# SCH_Alarm_Robotics_PCB_Hacker_Card_2024-.net
KiCad netlist of a schematic drawn in EasyEDA
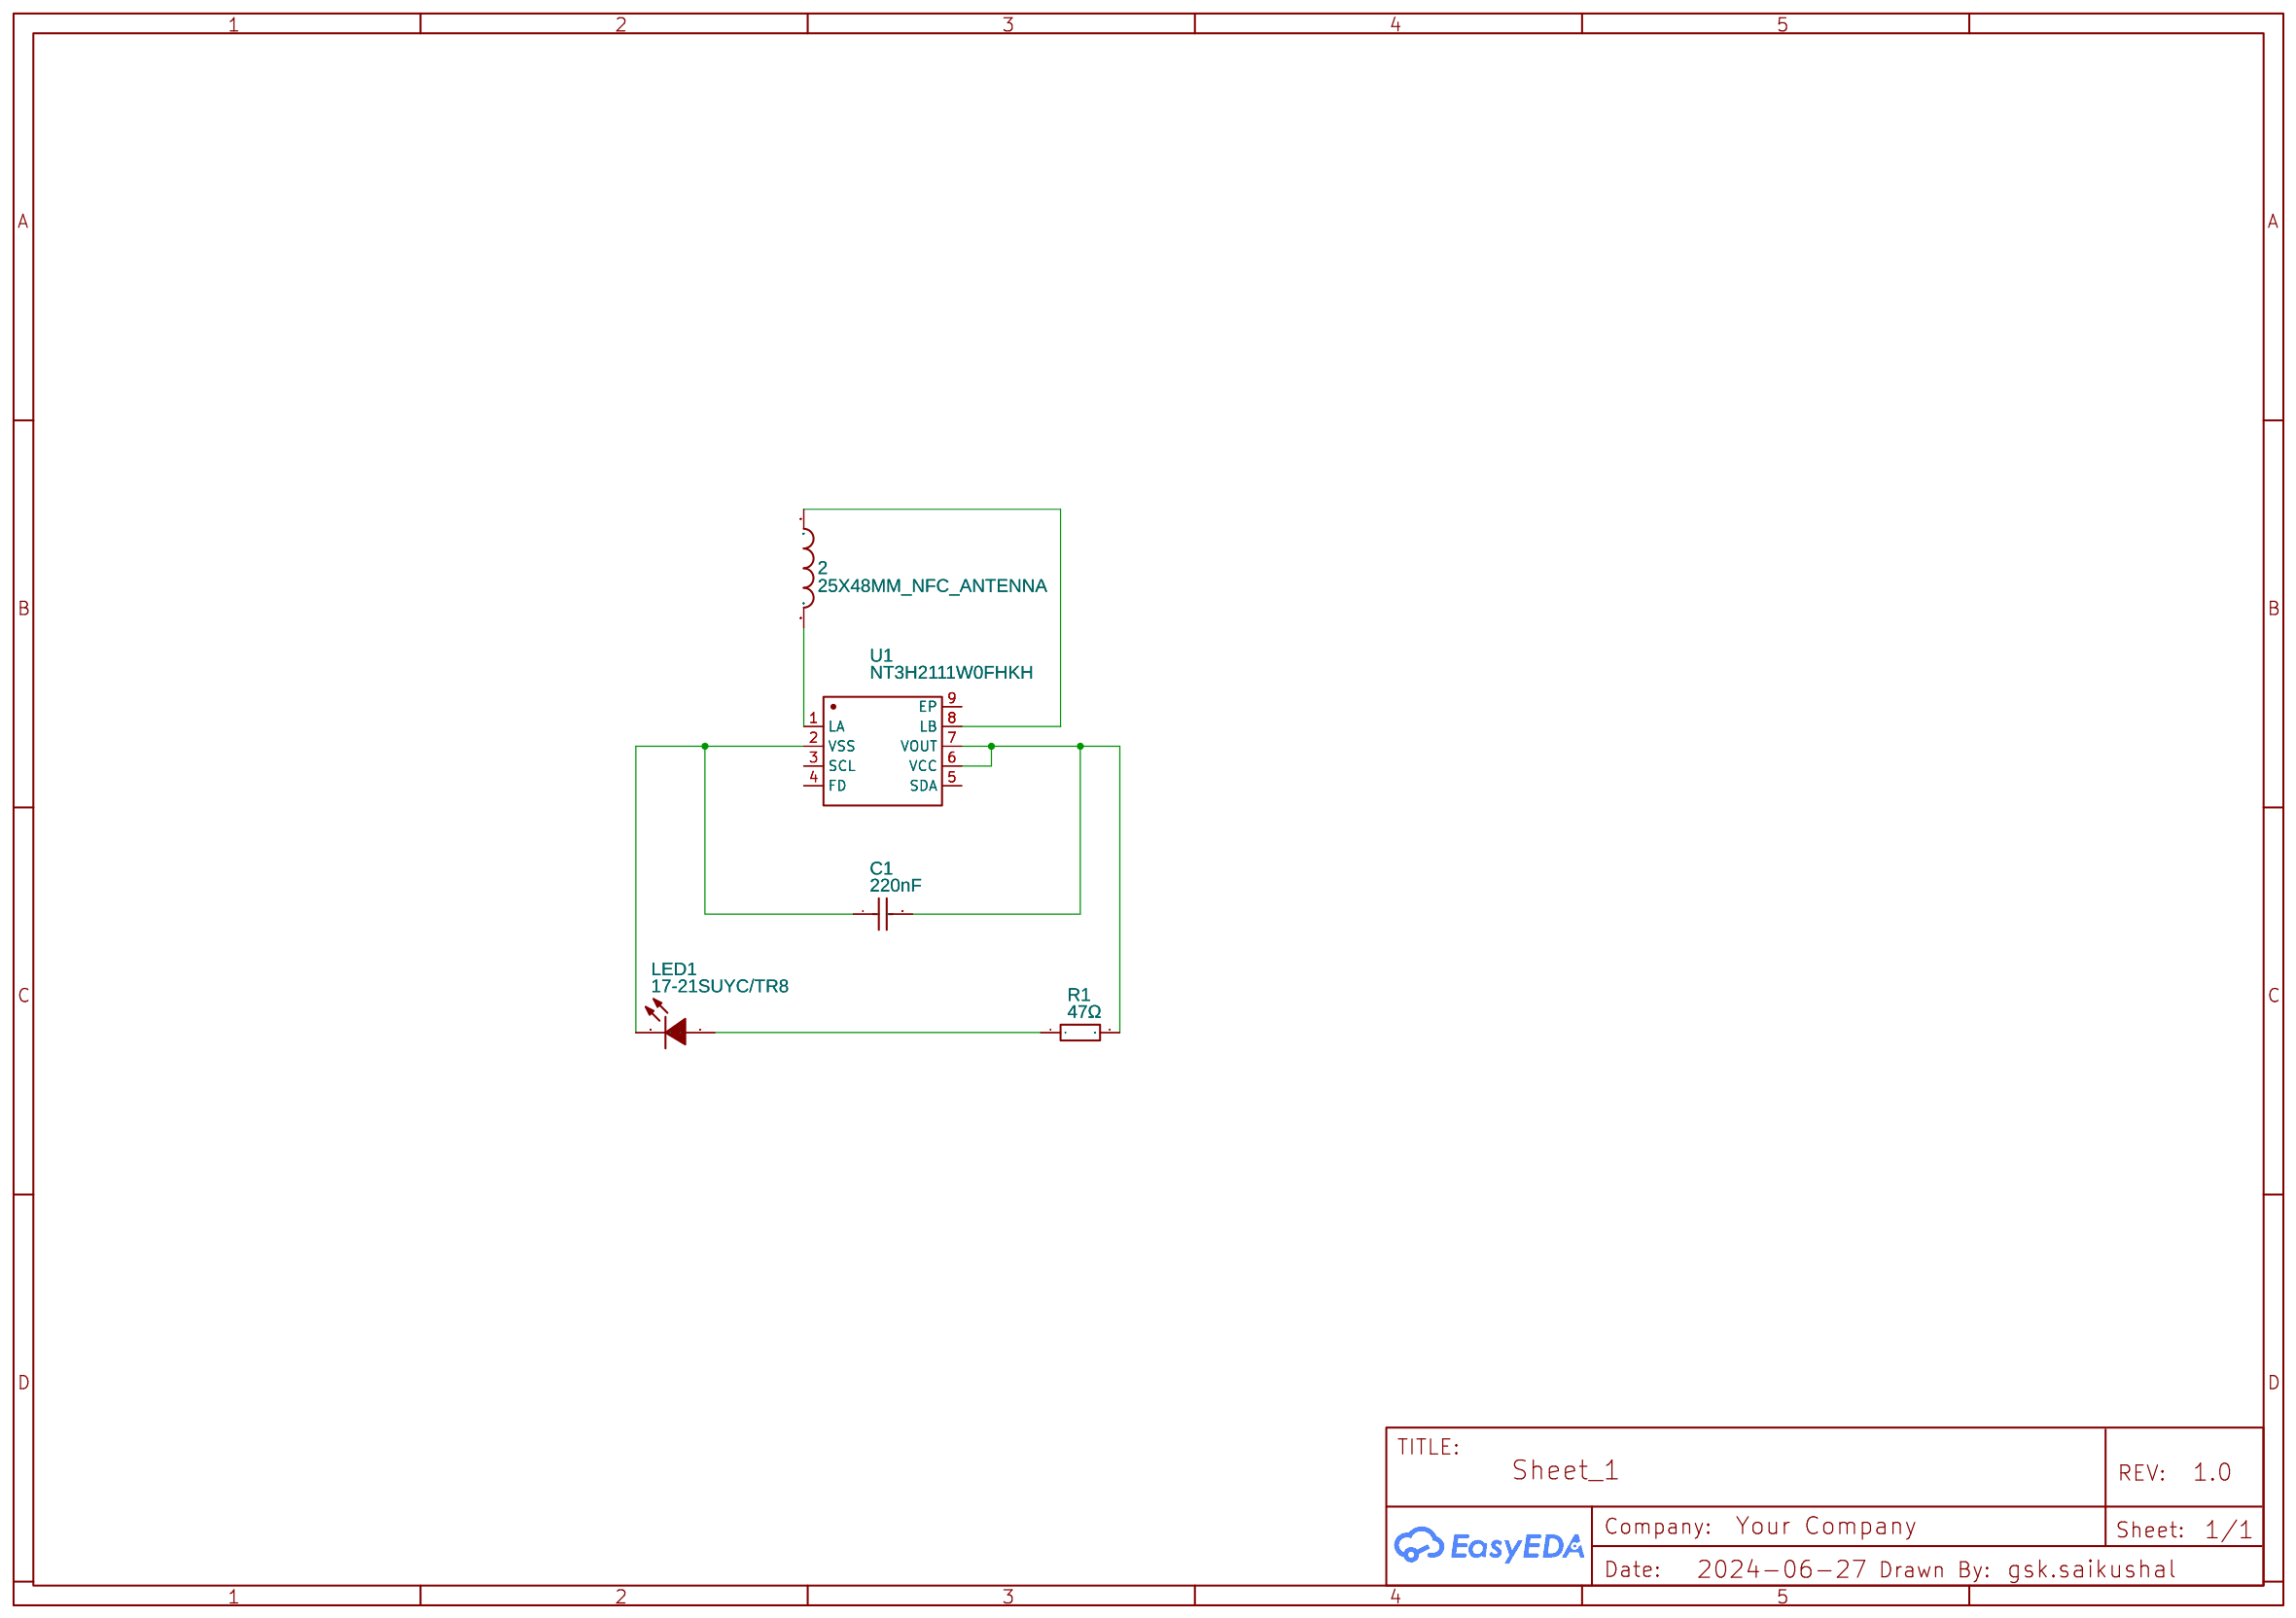
[diagram p0: schematic sheet]

(export (version "E")
  (design (tool "Eeschema 10.0.6"))
  (components
    (comp (ref "2") (value "25X48MM_NFC_ANTENNA") (libsource (lib "") (part "25X48MM_NFC_ANTENNA")))
    (comp (ref "C1")
      (value "220nF")
      (fields
        (field (name "Manufacturer Part") "CL10B224KA8NNNC")
        (field (name "Manufacturer") "SAMSUNG(三星)")
      )
      (libsource (lib "") (part "CL10B224KA8NNNC"))
    )
    (comp (ref "LED1")
      (value "17-21SUYC/TR8")
      (fields (field (name "Manufacturer Part") "KT-0805黄灯") (field (name "Manufacturer") "KENTO"))
      (libsource (lib "") (part "17-21SUYC/TR8"))
    )
    (comp (ref "R1")
      (value "47Ω")
      (fields
        (field (name "Manufacturer Part") "0603WAF470JT5E")
        (field (name "Manufacturer") "UNI-ROYAL(厚声)")
      )
      (libsource (lib "") (part "0603WAF470JT5E"))
    )
    (comp (ref "U1")
      (value "NT3H2111W0FHKH")
      (fields (field (name "Manufacturer") "NXP(恩智浦)"))
      (libsource (lib "") (part "NT3H2111W0FHKH"))
    )
  )
  (nets
    (net (code "1") (name "Net-(LED1-+)") (class "Default")
      (node (ref "LED1") (pin "1") (pinfunction "+_1") (pintype "unspecified"))
      (node (ref "R1") (pin "1") (pinfunction "1_1") (pintype "input"))
    )
    (net (code "2") (name "Net-(LED1--)") (class "Default")
      (node (ref "C1") (pin "1") (pinfunction "1_1") (pintype "input"))
      (node (ref "LED1") (pin "2") (pinfunction "-_2") (pintype "unspecified"))
      (node (ref "U1") (pin "2") (pinfunction "VSS_2") (pintype "unspecified"))
    )
    (net (code "3") (name "Net-(U1-LA)") (class "Default")
      (node (ref "2") (pin "P$2") (pinfunction "P$2_P$2") (pintype "bidirectional"))
      (node (ref "U1") (pin "1") (pinfunction "LA_1") (pintype "unspecified"))
    )
    (net (code "4") (name "Net-(U1-LB)") (class "Default")
      (node (ref "2") (pin "P$1") (pinfunction "P$1_P$1") (pintype "bidirectional"))
      (node (ref "U1") (pin "8") (pinfunction "LB_8") (pintype "unspecified"))
    )
    (net (code "5") (name "Net-(U1-VCC)") (class "Default")
      (node (ref "C1") (pin "2") (pinfunction "2_2") (pintype "input"))
      (node (ref "R1") (pin "2") (pinfunction "2_2") (pintype "input"))
      (node (ref "U1") (pin "6") (pinfunction "VCC_6") (pintype "unspecified"))
      (node (ref "U1") (pin "7") (pinfunction "VOUT_7") (pintype "unspecified"))
    )
    (net (code "6") (name "unconnected-(U1-EP-Pad9)") (class "Default")
      (node (ref "U1") (pin "9") (pinfunction "EP_9") (pintype "unspecified"))
    )
    (net (code "7") (name "unconnected-(U1-FD-Pad4)") (class "Default")
      (node (ref "U1") (pin "4") (pinfunction "FD_4") (pintype "unspecified"))
    )
    (net (code "8") (name "unconnected-(U1-SCL-Pad3)") (class "Default")
      (node (ref "U1") (pin "3") (pinfunction "SCL_3") (pintype "unspecified"))
    )
    (net (code "9") (name "unconnected-(U1-SDA-Pad5)") (class "Default")
      (node (ref "U1") (pin "5") (pinfunction "SDA_5") (pintype "unspecified"))
    )
  )
)
